# StratoChovy.net
KiCad netlist of a schematic drawn in Altium Designer
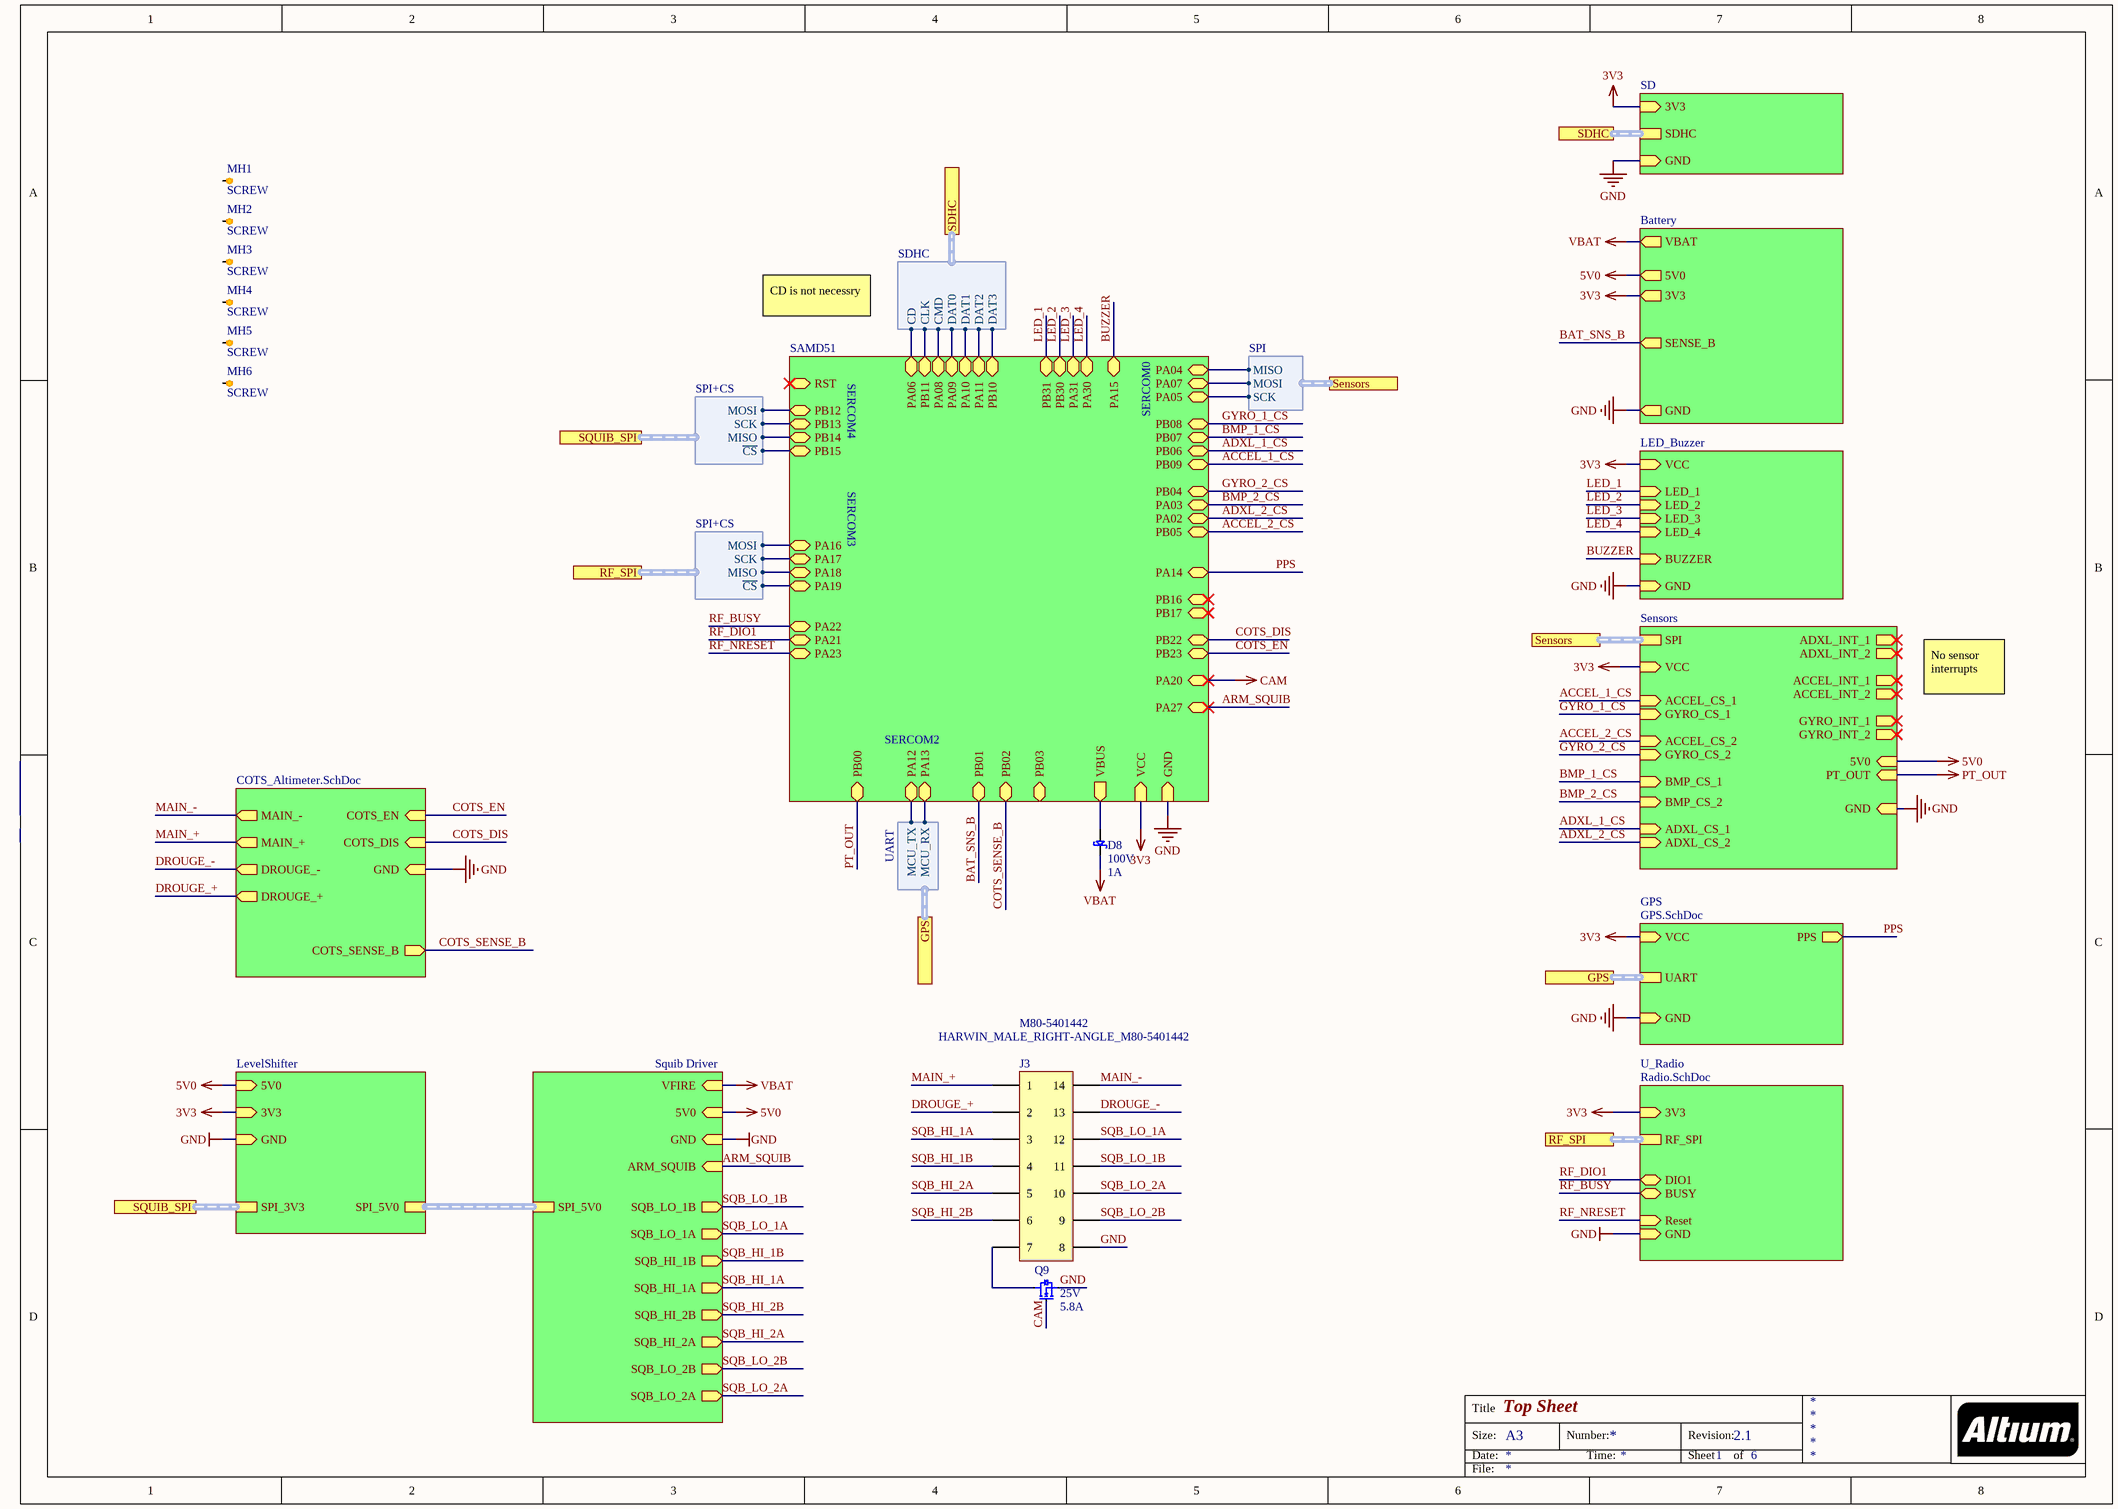
[diagram p0: StratoChovy.SchDoc]

(export (version "E")
  (design (tool "Eeschema 10.0.6"))
  (components
    (comp (ref "D8")
      (value "Diode_CD214A-B1100LF")
      (footprint "SMA")
      (description "Diode Schottky 100V 1A Surface Mount SMA (DO-214AC)")
      (fields
        (field (name "MANUFACTURER PART NUMBER") "CD214A-B1100LF")
        (field (name "VOLTAGE - DC REVERSE (VR) (MAX)") "100V")
        (field (name "CURRENT - AVERAGE RECTIFIED (IO)") "1A")
        (field (name "MANUFACTURER") "Bourns Inc.")
      )
      (libsource (lib "Stanford Student Space Initiative") (part "Diode_CD214A-B1100LF"))
    )
    (comp (ref "J3")
      (value "HARWIN_MALE_RIGHT-ANGLE_M80-5401442")
      (footprint "HARWIN_M80-5401442")
      (description "7+7 POS R/A MALE 3mm TAIL W/JS TIN")
      (fields (field (name "MANUFACTURER PART NUMBER") "M80-5401442") (field (name "MANUFACTURER") "Harwin"))
      (libsource (lib "") (part "Symbol_1"))
    )
    (comp (ref "MH1")
      (value "SCREW")
      (footprint "SCREW_M3")
      (libsource (lib "Stanford Student Space Initiative") (part "SCREW"))
    )
    (comp (ref "MH2")
      (value "SCREW")
      (footprint "SCREW_M3")
      (libsource (lib "Stanford Student Space Initiative") (part "SCREW"))
    )
    (comp (ref "MH3")
      (value "SCREW")
      (footprint "SCREW_M3")
      (libsource (lib "Stanford Student Space Initiative") (part "SCREW"))
    )
    (comp (ref "MH4")
      (value "SCREW")
      (footprint "SCREW_M3")
      (libsource (lib "Stanford Student Space Initiative") (part "SCREW"))
    )
    (comp (ref "MH5")
      (value "SCREW")
      (footprint "SCREW_M3")
      (libsource (lib "Stanford Student Space Initiative") (part "SCREW"))
    )
    (comp (ref "MH6")
      (value "SCREW")
      (footprint "SCREW_M3")
      (libsource (lib "Stanford Student Space Initiative") (part "SCREW"))
    )
    (comp (ref "Q9")
      (value "NFET_IRFML8244TRPBF")
      (footprint "3SOT23")
      (description "MOSFET N-CH 25V 5.8A SOT23")
      (fields
        (field (name "MANUFACTURER") "International Rectifier")
        (field (name "MANUFACTURER PART NUMBER") "IRFML8244TRPBF")
        (field (name "DRAIN TO SOURCE VOLTAGE (VDSS)") "25V")
        (field (name "CURRENT - CONTINUOUS DRAIN (ID) @ 25° C") "5.8A")
      )
      (libsource (lib "Stanford Student Space Initiative") (part "Symbol"))
    )
  )
  (nets
    (net (code "21") (name "/DROUGE_+") (class "Default")
      (node (ref "J3") (pin "2") (pinfunction "2_2") (pintype "passive"))
    )
    (net (code "22") (name "/DROUGE_-") (class "Default")
      (node (ref "J3") (pin "13") (pinfunction "13_13") (pintype "passive"))
    )
    (net (code "31") (name "/MAIN_+") (class "Default")
      (node (ref "J3") (pin "1") (pinfunction "1_1") (pintype "passive"))
    )
    (net (code "32") (name "/MAIN_-") (class "Default")
      (node (ref "J3") (pin "14") (pinfunction "14_14") (pintype "passive"))
    )
    (net (code "62") (name "/SQB_HI_1A") (class "Default")
      (node (ref "J3") (pin "3") (pinfunction "3_3") (pintype "passive"))
    )
    (net (code "63") (name "/SQB_HI_1B") (class "Default")
      (node (ref "J3") (pin "4") (pinfunction "4_4") (pintype "passive"))
    )
    (net (code "64") (name "/SQB_HI_2A") (class "Default")
      (node (ref "J3") (pin "5") (pinfunction "5_5") (pintype "passive"))
    )
    (net (code "65") (name "/SQB_HI_2B") (class "Default")
      (node (ref "J3") (pin "6") (pinfunction "6_6") (pintype "passive"))
    )
    (net (code "66") (name "/SQB_LO_1A") (class "Default")
      (node (ref "J3") (pin "12") (pinfunction "12_12") (pintype "passive"))
    )
    (net (code "67") (name "/SQB_LO_1B") (class "Default")
      (node (ref "J3") (pin "11") (pinfunction "11_11") (pintype "passive"))
    )
    (net (code "68") (name "/SQB_LO_2A") (class "Default")
      (node (ref "J3") (pin "10") (pinfunction "10_10") (pintype "passive"))
    )
    (net (code "69") (name "/SQB_LO_2B") (class "Default")
      (node (ref "J3") (pin "9") (pinfunction "9_9") (pintype "passive"))
    )
    (net (code "70") (name "/VBUS") (class "Default")
      (node (ref "D8") (pin "1") (pinfunction "Anode_1") (pintype "passive"))
    )
    (net (code "77") (name "CAM") (class "Default") (node (ref "Q9") (pin "1") (pintype "passive")))
    (net (code "78") (name "GND") (class "Default")
      (node (ref "J3") (pin "8") (pinfunction "8_8") (pintype "passive"))
      (node (ref "Q9") (pin "2") (pintype "passive"))
    )
    (net (code "79") (name "Net-(J3-Pad7)") (class "Default")
      (node (ref "J3") (pin "7") (pinfunction "7_7") (pintype "passive"))
      (node (ref "Q9") (pin "3") (pintype "passive"))
    )
    (net (code "81") (name "VBAT") (class "Default")
      (node (ref "D8") (pin "2") (pinfunction "Cathode_2") (pintype "passive"))
    )
    (net (code "82") (name "unconnected-(MH1-Pad1)") (class "Default")
      (node (ref "MH1") (pin "1") (pintype "passive"))
    )
    (net (code "83") (name "unconnected-(MH2-Pad1)") (class "Default")
      (node (ref "MH2") (pin "1") (pintype "passive"))
    )
    (net (code "84") (name "unconnected-(MH3-Pad1)") (class "Default")
      (node (ref "MH3") (pin "1") (pintype "passive"))
    )
    (net (code "85") (name "unconnected-(MH4-Pad1)") (class "Default")
      (node (ref "MH4") (pin "1") (pintype "passive"))
    )
    (net (code "86") (name "unconnected-(MH5-Pad1)") (class "Default")
      (node (ref "MH5") (pin "1") (pintype "passive"))
    )
    (net (code "87") (name "unconnected-(MH6-Pad1)") (class "Default")
      (node (ref "MH6") (pin "1") (pintype "passive"))
    )
  )
)
